# 4_cpu.net
KiCad netlist of a schematic drawn in Altium Designer
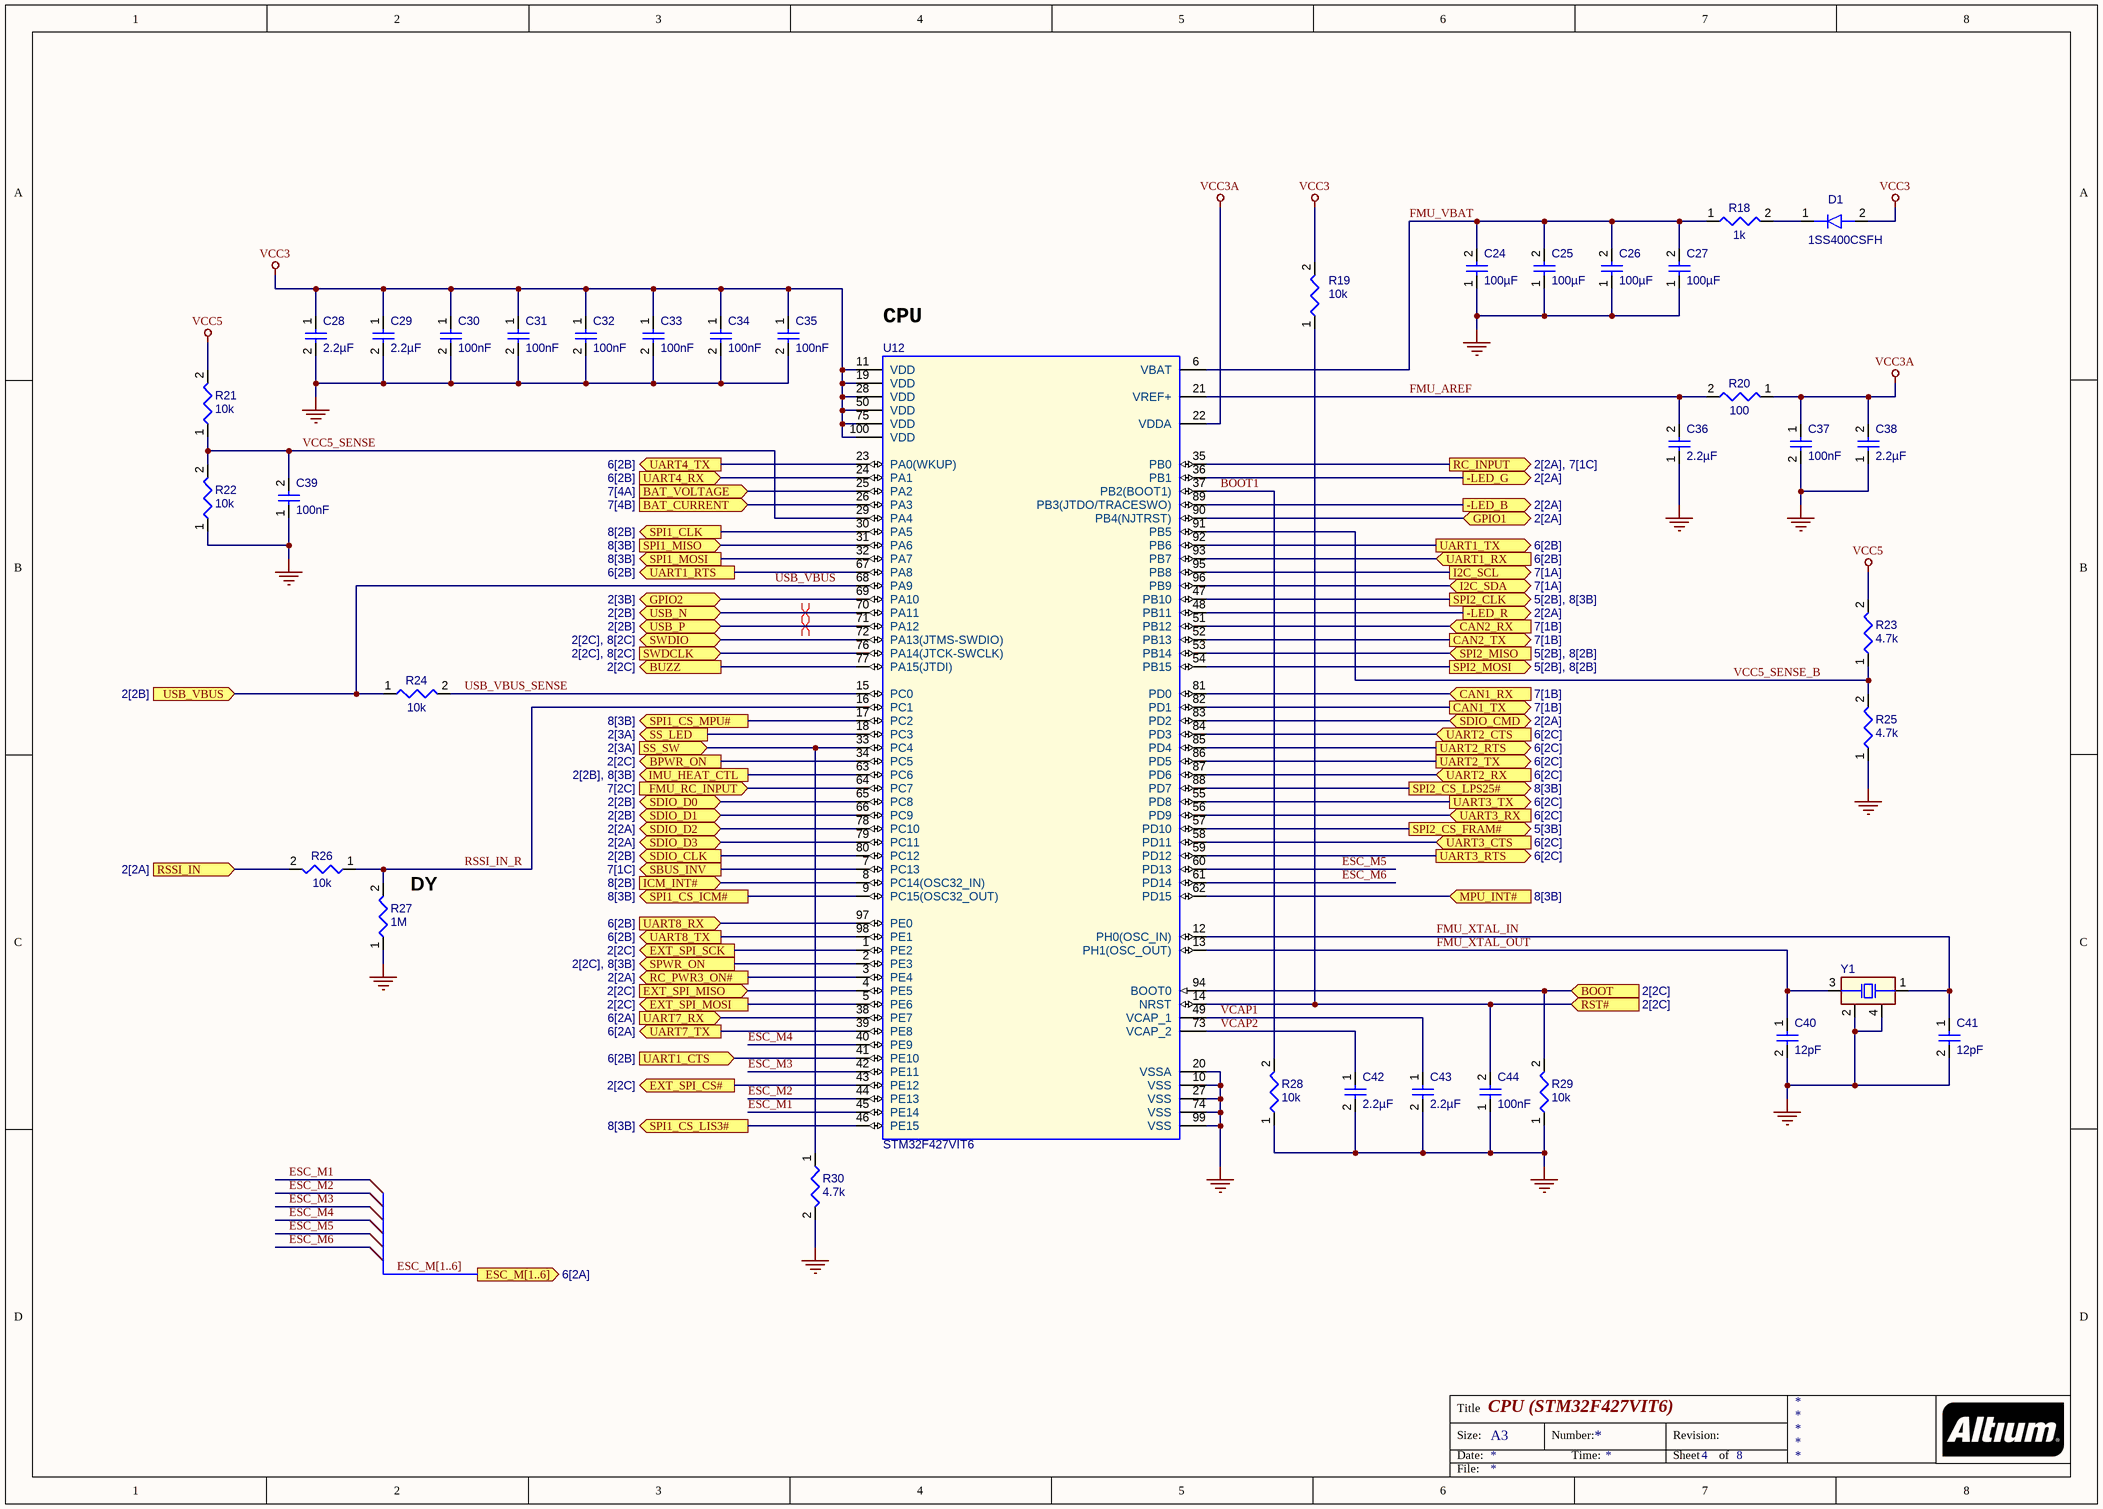
[diagram p0: 4_cpu.SchDoc]

(export (version "E")
  (design (tool "Eeschema 10.0.6"))
  (components
    (comp (ref "C24")
      (value "100µF")
      (footprint "CAPC0805(2012)145_L")
      (description "Chip Capacitor, 100µF +/-20%, 6.3V, 0805, Thickness 1.45 mm")
      (fields (field (name "TOLERANCE") "10%") (field (name "MANUFACTURER") "Murata"))
      (libsource (lib "Kame_FMU") (part "Capacitor 100µF +/-20% 6.3V 0805"))
    )
    (comp (ref "C25")
      (value "100µF")
      (footprint "CAPC0805(2012)145_L")
      (description "Chip Capacitor, 100µF +/-20%, 6.3V, 0805, Thickness 1.45 mm")
      (fields (field (name "TOLERANCE") "10%") (field (name "MANUFACTURER") "Murata"))
      (libsource (lib "Kame_FMU") (part "Capacitor 100µF +/-20% 6.3V 0805"))
    )
    (comp (ref "C26")
      (value "100µF")
      (footprint "CAPC0805(2012)145_L")
      (description "Chip Capacitor, 100µF +/-20%, 6.3V, 0805, Thickness 1.45 mm")
      (fields (field (name "TOLERANCE") "10%") (field (name "MANUFACTURER") "Murata"))
      (libsource (lib "Kame_FMU") (part "Capacitor 100µF +/-20% 6.3V 0805"))
    )
    (comp (ref "C27")
      (value "100µF")
      (footprint "CAPC0805(2012)145_L")
      (description "Chip Capacitor, 100µF +/-20%, 6.3V, 0805, Thickness 1.45 mm")
      (fields (field (name "TOLERANCE") "10%") (field (name "MANUFACTURER") "Murata"))
      (libsource (lib "Kame_FMU") (part "Capacitor 100µF +/-20% 6.3V 0805"))
    )
    (comp (ref "C28")
      (value "2.2µF")
      (footprint "CAPC0402(1005)60_L")
      (description "Chip Capacitor, 2,2µF +/-20%, 10V, 0402, Thickness 0.6 mm")
      (fields (field (name "TOLERANCE") "10%") (field (name "MANUFACTURER") "Murata"))
      (libsource (lib "Kame_FMU") (part "Capacitor 2,2µF +/-20% 10V 0402"))
    )
    (comp (ref "C29")
      (value "2.2µF")
      (footprint "CAPC0402(1005)60_L")
      (description "Chip Capacitor, 2,2µF +/-20%, 10V, 0402, Thickness 0.6 mm")
      (fields (field (name "TOLERANCE") "10%") (field (name "MANUFACTURER") "Murata"))
      (libsource (lib "Kame_FMU") (part "Capacitor 2,2µF +/-20% 10V 0402"))
    )
    (comp (ref "C30")
      (value "100nF")
      (footprint "CAPC0402(1005)60_L")
      (description "Chip Capacitor, 100nF +/-20%, 10V, 0402, Thickness 0.6 mm")
      (fields (field (name "TOLERANCE") "20%") (field (name "MANUFACTURER") "KEMET"))
      (libsource (lib "Kame_FMU") (part "Capacitor 100nF +/-20% 10V 0402"))
    )
    (comp (ref "C31")
      (value "100nF")
      (footprint "CAPC0402(1005)60_L")
      (description "Chip Capacitor, 100nF +/-20%, 10V, 0402, Thickness 0.6 mm")
      (fields (field (name "TOLERANCE") "20%") (field (name "MANUFACTURER") "KEMET"))
      (libsource (lib "Kame_FMU") (part "Capacitor 100nF +/-20% 10V 0402"))
    )
    (comp (ref "C32")
      (value "100nF")
      (footprint "CAPC0402(1005)60_L")
      (description "Chip Capacitor, 100nF +/-20%, 10V, 0402, Thickness 0.6 mm")
      (fields (field (name "TOLERANCE") "20%") (field (name "MANUFACTURER") "KEMET"))
      (libsource (lib "Kame_FMU") (part "Capacitor 100nF +/-20% 10V 0402"))
    )
    (comp (ref "C33")
      (value "100nF")
      (footprint "CAPC0402(1005)60_L")
      (description "Chip Capacitor, 100nF +/-20%, 10V, 0402, Thickness 0.6 mm")
      (fields (field (name "TOLERANCE") "20%") (field (name "MANUFACTURER") "KEMET"))
      (libsource (lib "Kame_FMU") (part "Capacitor 100nF +/-20% 10V 0402"))
    )
    (comp (ref "C34")
      (value "100nF")
      (footprint "CAPC0402(1005)60_L")
      (description "Chip Capacitor, 100nF +/-20%, 10V, 0402, Thickness 0.6 mm")
      (fields (field (name "TOLERANCE") "20%") (field (name "MANUFACTURER") "KEMET"))
      (libsource (lib "Kame_FMU") (part "Capacitor 100nF +/-20% 10V 0402"))
    )
    (comp (ref "C35")
      (value "100nF")
      (footprint "CAPC0402(1005)60_L")
      (description "Chip Capacitor, 100nF +/-20%, 10V, 0402, Thickness 0.6 mm")
      (fields (field (name "TOLERANCE") "20%") (field (name "MANUFACTURER") "KEMET"))
      (libsource (lib "Kame_FMU") (part "Capacitor 100nF +/-20% 10V 0402"))
    )
    (comp (ref "C36")
      (value "2.2µF")
      (footprint "CAPC0402(1005)60_L")
      (description "Chip Capacitor, 2,2µF +/-20%, 10V, 0402, Thickness 0.6 mm")
      (fields (field (name "TOLERANCE") "10%") (field (name "MANUFACTURER") "Murata"))
      (libsource (lib "Kame_FMU") (part "Capacitor 2,2µF +/-20% 10V 0402"))
    )
    (comp (ref "C37")
      (value "100nF")
      (footprint "CAPC0402(1005)60_L")
      (description "Chip Capacitor, 100nF +/-20%, 10V, 0402, Thickness 0.6 mm")
      (fields (field (name "TOLERANCE") "20%") (field (name "MANUFACTURER") "KEMET"))
      (libsource (lib "Kame_FMU") (part "Capacitor 100nF +/-20% 10V 0402"))
    )
    (comp (ref "C38")
      (value "2.2µF")
      (footprint "CAPC0402(1005)60_L")
      (description "Chip Capacitor, 2,2µF +/-20%, 10V, 0402, Thickness 0.6 mm")
      (fields (field (name "TOLERANCE") "10%") (field (name "MANUFACTURER") "Murata"))
      (libsource (lib "Kame_FMU") (part "Capacitor 2,2µF +/-20% 10V 0402"))
    )
    (comp (ref "C39")
      (value "100nF")
      (footprint "CAPC0402(1005)60_L")
      (description "Chip Capacitor, 100nF +/-20%, 10V, 0402, Thickness 0.6 mm")
      (fields (field (name "TOLERANCE") "20%") (field (name "MANUFACTURER") "KEMET"))
      (libsource (lib "Kame_FMU") (part "Capacitor 100nF +/-20% 10V 0402"))
    )
    (comp (ref "C40")
      (value "12pF")
      (footprint "CAPC0402(1005)33_L")
      (description "Chip Capacitor, 12pF +/-10%, 50V, 0402, Thickness 0.33 mm")
      (fields (field (name "TOLERANCE") "20%") (field (name "MANUFACTURER") "Murata"))
      (libsource (lib "Kame_FMU") (part "Capacitor 12pF +/-10% 50V 0402"))
    )
    (comp (ref "C41")
      (value "12pF")
      (footprint "CAPC0402(1005)33_L")
      (description "Chip Capacitor, 12pF +/-10%, 50V, 0402, Thickness 0.33 mm")
      (fields (field (name "TOLERANCE") "20%") (field (name "MANUFACTURER") "Murata"))
      (libsource (lib "Kame_FMU") (part "Capacitor 12pF +/-10% 50V 0402"))
    )
    (comp (ref "C42")
      (value "2.2µF")
      (footprint "CAPC0402(1005)60_L")
      (description "Chip Capacitor, 2,2µF +/-20%, 10V, 0402, Thickness 0.6 mm")
      (fields (field (name "TOLERANCE") "10%") (field (name "MANUFACTURER") "Murata"))
      (libsource (lib "Kame_FMU") (part "Capacitor 2,2µF +/-20% 10V 0402"))
    )
    (comp (ref "C43")
      (value "2.2µF")
      (footprint "CAPC0402(1005)60_L")
      (description "Chip Capacitor, 2,2µF +/-20%, 10V, 0402, Thickness 0.6 mm")
      (fields (field (name "TOLERANCE") "10%") (field (name "MANUFACTURER") "Murata"))
      (libsource (lib "Kame_FMU") (part "Capacitor 2,2µF +/-20% 10V 0402"))
    )
    (comp (ref "C44")
      (value "100nF")
      (footprint "CAPC0402(1005)60_L")
      (description "Chip Capacitor, 100nF +/-20%, 10V, 0402, Thickness 0.6 mm")
      (fields (field (name "TOLERANCE") "20%") (field (name "MANUFACTURER") "KEMET"))
      (libsource (lib "Kame_FMU") (part "Capacitor 100nF +/-20% 10V 0402"))
    )
    (comp (ref "D1")
      (value "1SS400CSFH")
      (footprint "ROHM-VMN2-2_V")
      (description "Switching Diode (High Speed Switching), 80 V, 100 mA, 2-Pin SOD-923, RoHS, Tape and Reel")
      (fields (field (name "MANUFACTURER") "Rohm") (field (name "MANUFACTURER PART NUMBER") "1SS400CSFHT2RA"))
      (libsource (lib "Kame_FMU") (part "1SS400CSFH"))
    )
    (comp (ref "R18")
      (value "1k")
      (footprint "RESC0402(1005)_L")
      (description "Chip Resistor, 1 kOhms, +/-5 %, 63 mW, -55 to 155 degC, 0402")
      (fields (field (name "TOLERANCE") "5%") (field (name "POWER") "63mW"))
      (libsource (lib "Kame_FMU") (part "Resistor 1K +/-5 % 0402 63 mW"))
    )
    (comp (ref "R19")
      (value "10k")
      (footprint "RESC0402(1005)_L")
      (description "Chip Resistor, 10 kOhms, +/-1 %, 63 mW, -55 to 125 degC, 0402")
      (fields (field (name "TOLERANCE") "1%") (field (name "POWER") "63mW"))
      (libsource (lib "Kame_FMU") (part "Resistor 10K  +/-1 % 0402 63 mW"))
    )
    (comp (ref "R20")
      (value "100")
      (footprint "RESC0402(1005)_L")
      (description "Chip Resistor, 100 Ohms, +/-1 %, 63 mW, -55 to 155 degC, 0402")
      (fields (field (name "TOLERANCE") "1%") (field (name "POWER") "63mW"))
      (libsource (lib "Kame_FMU") (part "Resistor 100R +/-1 % 0402 63 mW"))
    )
    (comp (ref "R21")
      (value "10k")
      (footprint "RESC0402(1005)_L")
      (description "Chip Resistor, 10 kOhms, +/-1 %, 63 mW, -55 to 125 degC, 0402")
      (fields (field (name "TOLERANCE") "1%") (field (name "POWER") "63mW"))
      (libsource (lib "Kame_FMU") (part "Resistor 10K  +/-1 % 0402 63 mW"))
    )
    (comp (ref "R22")
      (value "10k")
      (footprint "RESC0402(1005)_L")
      (description "Chip Resistor, 10 kOhms, +/-1 %, 63 mW, -55 to 125 degC, 0402")
      (fields (field (name "TOLERANCE") "1%") (field (name "POWER") "63mW"))
      (libsource (lib "Kame_FMU") (part "Resistor 10K  +/-1 % 0402 63 mW"))
    )
    (comp (ref "R23")
      (value "4.7k")
      (footprint "RESC0402(1005)_L")
      (description "Chip Resistor, 4,7 kOhms, +/-1 %, 63 mW, -55 to 155 degC, 0402")
      (fields (field (name "TOLERANCE") "1%") (field (name "POWER") "63mW"))
      (libsource (lib "Kame_FMU") (part "Resistor 4K7  +/-1 % 0402 63 mW"))
    )
    (comp (ref "R24")
      (value "10k")
      (footprint "RESC0402(1005)_L")
      (description "Chip Resistor, 10 kOhms, +/-1 %, 63 mW, -55 to 125 degC, 0402")
      (fields (field (name "TOLERANCE") "1%") (field (name "POWER") "63mW"))
      (libsource (lib "Kame_FMU") (part "Resistor 10K  +/-1 % 0402 63 mW"))
    )
    (comp (ref "R25")
      (value "4.7k")
      (footprint "RESC0402(1005)_L")
      (description "Chip Resistor, 4,7 kOhms, +/-1 %, 63 mW, -55 to 155 degC, 0402")
      (fields (field (name "TOLERANCE") "1%") (field (name "POWER") "63mW"))
      (libsource (lib "Kame_FMU") (part "Resistor 4K7  +/-1 % 0402 63 mW"))
    )
    (comp (ref "R26")
      (value "10k")
      (footprint "RESC0402(1005)_L")
      (description "Chip Resistor, 10 kOhms, +/-1 %, 63 mW, -55 to 125 degC, 0402")
      (fields (field (name "TOLERANCE") "1%") (field (name "POWER") "63mW"))
      (libsource (lib "Kame_FMU") (part "Resistor 10K  +/-1 % 0402 63 mW"))
    )
    (comp (ref "R27")
      (value "1M")
      (footprint "RESC0402(1005)_L")
      (description "Chip Resistor, 1 MOhms, +/-5 %, 63 mW, -55 to 155 degC, 0402")
      (fields (field (name "TOLERANCE") "5%") (field (name "POWER") "63mW"))
      (libsource (lib "Kame_FMU") (part "Resistor 1M +/-5 % 0402 63 mW"))
    )
    (comp (ref "R28")
      (value "10k")
      (footprint "RESC0402(1005)_L")
      (description "Chip Resistor, 10 kOhms, +/-1 %, 63 mW, -55 to 125 degC, 0402")
      (fields (field (name "TOLERANCE") "1%") (field (name "POWER") "63mW"))
      (libsource (lib "Kame_FMU") (part "Resistor 10K  +/-1 % 0402 63 mW"))
    )
    (comp (ref "R29")
      (value "10k")
      (footprint "RESC0402(1005)_L")
      (description "Chip Resistor, 10 kOhms, +/-1 %, 63 mW, -55 to 125 degC, 0402")
      (fields (field (name "TOLERANCE") "1%") (field (name "POWER") "63mW"))
      (libsource (lib "Kame_FMU") (part "Resistor 10K  +/-1 % 0402 63 mW"))
    )
    (comp (ref "R30")
      (value "4.7k")
      (footprint "RESC0402(1005)_L")
      (description "Chip Resistor, 4,7 kOhms, +/-1 %, 63 mW, -55 to 155 degC, 0402")
      (fields (field (name "TOLERANCE") "1%") (field (name "POWER") "63mW"))
      (libsource (lib "Kame_FMU") (part "Resistor 4K7  +/-1 % 0402 63 mW"))
    )
    (comp (ref "U12")
      (value "STM32F427VIT6")
      (footprint "STM-LQFP100")
      (libsource (lib "Kame_FMU") (part "STM32F427VIT6"))
    )
    (comp (ref "Y1")
      (value "FA-12824.0000MF10Z-W3")
      (footprint "EPSON-FA-128_V")
      (description "Crystal, 24 MHz, +/- 10 ppm, -20 to 75 degC, 4-Pin SMD, RoHS, Tape and Reel")
      (fields (field (name "MANUFACTURER") "Epson"))
      (libsource (lib "Kame_FMU") (part "FA-12824.0000MF10Z-W3"))
    )
  )
  (nets
    (net (code "1") (name "/-LED_B") (class "Default")
      (node (ref "U12") (pin "89") (pinfunction "PB3(JTDO/TRACESWO)_89") (pintype "bidirectional"))
    )
    (net (code "2") (name "/-LED_G") (class "Default")
      (node (ref "U12") (pin "36") (pinfunction "PB1_36") (pintype "bidirectional"))
    )
    (net (code "3") (name "/-LED_R") (class "Default")
      (node (ref "U12") (pin "48") (pinfunction "PB11_48") (pintype "bidirectional"))
    )
    (net (code "4") (name "/BAT_CURRENT") (class "Default")
      (node (ref "U12") (pin "26") (pinfunction "PA3_26") (pintype "bidirectional"))
    )
    (net (code "5") (name "/BAT_VOLTAGE") (class "Default")
      (node (ref "U12") (pin "25") (pinfunction "PA2_25") (pintype "bidirectional"))
    )
    (net (code "6") (name "/BOOT") (class "Default")
      (node (ref "R29") (pin "2") (pinfunction "2_2") (pintype "passive"))
      (node (ref "U12") (pin "94") (pinfunction "BOOT0_94") (pintype "input"))
    )
    (net (code "7") (name "/BOOT1") (class "Default")
      (node (ref "R28") (pin "2") (pinfunction "2_2") (pintype "passive"))
      (node (ref "U12") (pin "37") (pinfunction "PB2(BOOT1)_37") (pintype "bidirectional"))
    )
    (net (code "8") (name "/BPWR_ON") (class "Default")
      (node (ref "U12") (pin "34") (pinfunction "PC5_34") (pintype "bidirectional"))
    )
    (net (code "9") (name "/BUZZ") (class "Default")
      (node (ref "U12") (pin "77") (pinfunction "PA15(JTDI)_77") (pintype "bidirectional"))
    )
    (net (code "10") (name "/CAN1_RX") (class "Default")
      (node (ref "U12") (pin "81") (pinfunction "PD0_81") (pintype "bidirectional"))
    )
    (net (code "11") (name "/CAN1_TX") (class "Default")
      (node (ref "U12") (pin "82") (pinfunction "PD1_82") (pintype "bidirectional"))
    )
    (net (code "12") (name "/CAN2_RX") (class "Default")
      (node (ref "U12") (pin "51") (pinfunction "PB12_51") (pintype "bidirectional"))
    )
    (net (code "13") (name "/CAN2_TX") (class "Default")
      (node (ref "U12") (pin "52") (pinfunction "PB13_52") (pintype "bidirectional"))
    )
    (net (code "14") (name "/ESC_M1") (class "Default")
      (node (ref "U12") (pin "45") (pinfunction "PE14_45") (pintype "bidirectional"))
    )
    (net (code "15") (name "/ESC_M2") (class "Default")
      (node (ref "U12") (pin "44") (pinfunction "PE13_44") (pintype "bidirectional"))
    )
    (net (code "16") (name "/ESC_M3") (class "Default")
      (node (ref "U12") (pin "42") (pinfunction "PE11_42") (pintype "bidirectional"))
    )
    (net (code "17") (name "/ESC_M4") (class "Default")
      (node (ref "U12") (pin "40") (pinfunction "PE9_40") (pintype "bidirectional"))
    )
    (net (code "18") (name "/ESC_M5") (class "Default")
      (node (ref "U12") (pin "60") (pinfunction "PD13_60") (pintype "bidirectional"))
    )
    (net (code "19") (name "/ESC_M6") (class "Default")
      (node (ref "U12") (pin "61") (pinfunction "PD14_61") (pintype "bidirectional"))
    )
    (net (code "21") (name "/EXT_SPI_CS#") (class "Default")
      (node (ref "U12") (pin "43") (pinfunction "PE12_43") (pintype "bidirectional"))
    )
    (net (code "22") (name "/EXT_SPI_MISO") (class "Default")
      (node (ref "U12") (pin "4") (pinfunction "PE5_4") (pintype "bidirectional"))
    )
    (net (code "23") (name "/EXT_SPI_MOSI") (class "Default")
      (node (ref "U12") (pin "5") (pinfunction "PE6_5") (pintype "bidirectional"))
    )
    (net (code "24") (name "/EXT_SPI_SCK") (class "Default")
      (node (ref "U12") (pin "1") (pinfunction "PE2_1") (pintype "bidirectional"))
    )
    (net (code "25") (name "/FMU_AREF") (class "Default")
      (node (ref "C36") (pin "2") (pinfunction "2_2") (pintype "passive"))
      (node (ref "R20") (pin "2") (pinfunction "2_2") (pintype "passive"))
      (node (ref "U12") (pin "21") (pinfunction "VREF+_21") (pintype "power_in"))
    )
    (net (code "26") (name "/FMU_RC_INPUT") (class "Default")
      (node (ref "U12") (pin "64") (pinfunction "PC7_64") (pintype "bidirectional"))
    )
    (net (code "27") (name "/FMU_VBAT") (class "Default")
      (node (ref "C24") (pin "2") (pinfunction "2_2") (pintype "passive"))
      (node (ref "C25") (pin "2") (pinfunction "2_2") (pintype "passive"))
      (node (ref "C26") (pin "2") (pinfunction "2_2") (pintype "passive"))
      (node (ref "C27") (pin "2") (pinfunction "2_2") (pintype "passive"))
      (node (ref "R18") (pin "1") (pinfunction "1_1") (pintype "passive"))
      (node (ref "U12") (pin "6") (pinfunction "VBAT_6") (pintype "power_in"))
    )
    (net (code "28") (name "/FMU_XTAL_IN") (class "Default")
      (node (ref "C41") (pin "1") (pinfunction "1_1") (pintype "passive"))
      (node (ref "U12") (pin "12") (pinfunction "PH0(OSC_IN)_12") (pintype "bidirectional"))
      (node (ref "Y1") (pin "1") (pinfunction "X1_1") (pintype "passive"))
    )
    (net (code "29") (name "/FMU_XTAL_OUT") (class "Default")
      (node (ref "C40") (pin "1") (pinfunction "1_1") (pintype "passive"))
      (node (ref "U12") (pin "13") (pinfunction "PH1(OSC_OUT)_13") (pintype "bidirectional"))
      (node (ref "Y1") (pin "3") (pinfunction "X2_3") (pintype "passive"))
    )
    (net (code "30") (name "/GPIO1") (class "Default")
      (node (ref "U12") (pin "90") (pinfunction "PB4(NJTRST)_90") (pintype "bidirectional"))
    )
    (net (code "31") (name "/GPIO2") (class "Default")
      (node (ref "U12") (pin "69") (pinfunction "PA10_69") (pintype "bidirectional"))
    )
    (net (code "32") (name "/I2C_SCL") (class "Default")
      (node (ref "U12") (pin "95") (pinfunction "PB8_95") (pintype "bidirectional"))
    )
    (net (code "33") (name "/I2C_SDA") (class "Default")
      (node (ref "U12") (pin "96") (pinfunction "PB9_96") (pintype "bidirectional"))
    )
    (net (code "34") (name "/ICM_INT#") (class "Default")
      (node (ref "U12") (pin "8") (pinfunction "PC14(OSC32_IN)_8") (pintype "bidirectional"))
    )
    (net (code "35") (name "/IMU_HEAT_CTL") (class "Default")
      (node (ref "U12") (pin "63") (pinfunction "PC6_63") (pintype "bidirectional"))
    )
    (net (code "36") (name "/MPU_INT#") (class "Default")
      (node (ref "U12") (pin "62") (pinfunction "PD15_62") (pintype "bidirectional"))
    )
    (net (code "37") (name "/RC_INPUT") (class "Default")
      (node (ref "U12") (pin "35") (pinfunction "PB0_35") (pintype "bidirectional"))
    )
    (net (code "38") (name "/RC_PWR3_ON#") (class "Default")
      (node (ref "U12") (pin "3") (pinfunction "PE4_3") (pintype "bidirectional"))
    )
    (net (code "39") (name "/RSSI_IN") (class "Default")
      (node (ref "R26") (pin "2") (pinfunction "2_2") (pintype "passive"))
    )
    (net (code "40") (name "/RSSI_IN_R") (class "Default")
      (node (ref "R26") (pin "1") (pinfunction "1_1") (pintype "passive"))
      (node (ref "R27") (pin "2") (pinfunction "2_2") (pintype "passive"))
      (node (ref "U12") (pin "16") (pinfunction "PC1_16") (pintype "bidirectional"))
    )
    (net (code "41") (name "/RST#") (class "Default")
      (node (ref "C44") (pin "2") (pinfunction "2_2") (pintype "passive"))
      (node (ref "R19") (pin "1") (pinfunction "1_1") (pintype "passive"))
      (node (ref "U12") (pin "14") (pinfunction "NRST_14") (pintype "bidirectional"))
    )
    (net (code "42") (name "/SBUS_INV") (class "Default")
      (node (ref "U12") (pin "7") (pinfunction "PC13_7") (pintype "bidirectional"))
    )
    (net (code "43") (name "/SDIO_CLK") (class "Default")
      (node (ref "U12") (pin "80") (pinfunction "PC12_80") (pintype "bidirectional"))
    )
    (net (code "44") (name "/SDIO_CMD") (class "Default")
      (node (ref "U12") (pin "83") (pinfunction "PD2_83") (pintype "bidirectional"))
    )
    (net (code "45") (name "/SDIO_D0") (class "Default")
      (node (ref "U12") (pin "65") (pinfunction "PC8_65") (pintype "bidirectional"))
    )
    (net (code "46") (name "/SDIO_D1") (class "Default")
      (node (ref "U12") (pin "66") (pinfunction "PC9_66") (pintype "bidirectional"))
    )
    (net (code "47") (name "/SDIO_D2") (class "Default")
      (node (ref "U12") (pin "78") (pinfunction "PC10_78") (pintype "bidirectional"))
    )
    (net (code "48") (name "/SDIO_D3") (class "Default")
      (node (ref "U12") (pin "79") (pinfunction "PC11_79") (pintype "bidirectional"))
    )
    (net (code "49") (name "/SPI1_CLK") (class "Default")
      (node (ref "U12") (pin "30") (pinfunction "PA5_30") (pintype "bidirectional"))
    )
    (net (code "50") (name "/SPI1_CS_ICM#") (class "Default")
      (node (ref "U12") (pin "9") (pinfunction "PC15(OSC32_OUT)_9") (pintype "bidirectional"))
    )
    (net (code "51") (name "/SPI1_CS_LIS3#") (class "Default")
      (node (ref "U12") (pin "46") (pinfunction "PE15_46") (pintype "bidirectional"))
    )
    (net (code "52") (name "/SPI1_CS_MPU#") (class "Default")
      (node (ref "U12") (pin "17") (pinfunction "PC2_17") (pintype "bidirectional"))
    )
    (net (code "53") (name "/SPI1_MISO") (class "Default")
      (node (ref "U12") (pin "31") (pinfunction "PA6_31") (pintype "bidirectional"))
    )
    (net (code "54") (name "/SPI1_MOSI") (class "Default")
      (node (ref "U12") (pin "32") (pinfunction "PA7_32") (pintype "bidirectional"))
    )
    (net (code "55") (name "/SPI2_CLK") (class "Default")
      (node (ref "U12") (pin "47") (pinfunction "PB10_47") (pintype "bidirectional"))
    )
    (net (code "56") (name "/SPI2_CS_FRAM#") (class "Default")
      (node (ref "U12") (pin "57") (pinfunction "PD10_57") (pintype "bidirectional"))
    )
    (net (code "57") (name "/SPI2_CS_LPS25#") (class "Default")
      (node (ref "U12") (pin "88") (pinfunction "PD7_88") (pintype "bidirectional"))
    )
    (net (code "58") (name "/SPI2_MISO") (class "Default")
      (node (ref "U12") (pin "53") (pinfunction "PB14_53") (pintype "bidirectional"))
    )
    (net (code "59") (name "/SPI2_MOSI") (class "Default")
      (node (ref "U12") (pin "54") (pinfunction "PB15_54") (pintype "bidirectional"))
    )
    (net (code "60") (name "/SPWR_ON") (class "Default")
      (node (ref "U12") (pin "2") (pinfunction "PE3_2") (pintype "bidirectional"))
    )
    (net (code "61") (name "/SS_LED") (class "Default")
      (node (ref "U12") (pin "18") (pinfunction "PC3_18") (pintype "bidirectional"))
    )
    (net (code "62") (name "/SS_SW") (class "Default")
      (node (ref "R30") (pin "1") (pinfunction "1_1") (pintype "passive"))
      (node (ref "U12") (pin "33") (pinfunction "PC4_33") (pintype "bidirectional"))
    )
    (net (code "63") (name "/SWDCLK") (class "Default")
      (node (ref "U12") (pin "76") (pinfunction "PA14(JTCK-SWCLK)_76") (pintype "bidirectional"))
    )
    (net (code "64") (name "/SWDIO") (class "Default")
      (node (ref "U12") (pin "72") (pinfunction "PA13(JTMS-SWDIO)_72") (pintype "bidirectional"))
    )
    (net (code "65") (name "/UART1_CTS") (class "Default")
      (node (ref "U12") (pin "41") (pinfunction "PE10_41") (pintype "bidirectional"))
    )
    (net (code "66") (name "/UART1_RTS") (class "Default")
      (node (ref "U12") (pin "67") (pinfunction "PA8_67") (pintype "bidirectional"))
    )
    (net (code "67") (name "/UART1_RX") (class "Default")
      (node (ref "U12") (pin "93") (pinfunction "PB7_93") (pintype "bidirectional"))
    )
    (net (code "68") (name "/UART1_TX") (class "Default")
      (node (ref "U12") (pin "92") (pinfunction "PB6_92") (pintype "bidirectional"))
    )
    (net (code "69") (name "/UART2_CTS") (class "Default")
      (node (ref "U12") (pin "84") (pinfunction "PD3_84") (pintype "bidirectional"))
    )
    (net (code "70") (name "/UART2_RTS") (class "Default")
      (node (ref "U12") (pin "85") (pinfunction "PD4_85") (pintype "bidirectional"))
    )
    (net (code "71") (name "/UART2_RX") (class "Default")
      (node (ref "U12") (pin "87") (pinfunction "PD6_87") (pintype "bidirectional"))
    )
    (net (code "72") (name "/UART2_TX") (class "Default")
      (node (ref "U12") (pin "86") (pinfunction "PD5_86") (pintype "bidirectional"))
    )
    (net (code "73") (name "/UART3_CTS") (class "Default")
      (node (ref "U12") (pin "58") (pinfunction "PD11_58") (pintype "bidirectional"))
    )
    (net (code "74") (name "/UART3_RTS") (class "Default")
      (node (ref "U12") (pin "59") (pinfunction "PD12_59") (pintype "bidirectional"))
    )
    (net (code "75") (name "/UART3_RX") (class "Default")
      (node (ref "U12") (pin "56") (pinfunction "PD9_56") (pintype "bidirectional"))
    )
    (net (code "76") (name "/UART3_TX") (class "Default")
      (node (ref "U12") (pin "55") (pinfunction "PD8_55") (pintype "bidirectional"))
    )
    (net (code "77") (name "/UART4_RX") (class "Default")
      (node (ref "U12") (pin "24") (pinfunction "PA1_24") (pintype "bidirectional"))
    )
    (net (code "78") (name "/UART4_TX") (class "Default")
      (node (ref "U12") (pin "23") (pinfunction "PA0(WKUP)_23") (pintype "bidirectional"))
    )
    (net (code "79") (name "/UART7_RX") (class "Default")
      (node (ref "U12") (pin "38") (pinfunction "PE7_38") (pintype "bidirectional"))
    )
    (net (code "80") (name "/UART7_TX") (class "Default")
      (node (ref "U12") (pin "39") (pinfunction "PE8_39") (pintype "bidirectional"))
    )
    (net (code "81") (name "/UART8_RX") (class "Default")
      (node (ref "U12") (pin "97") (pinfunction "PE0_97") (pintype "bidirectional"))
    )
    (net (code "82") (name "/UART8_TX") (class "Default")
      (node (ref "U12") (pin "98") (pinfunction "PE1_98") (pintype "bidirectional"))
    )
    (net (code "83") (name "/USB_N") (class "Default")
      (node (ref "U12") (pin "70") (pinfunction "PA11_70") (pintype "bidirectional"))
    )
    (net (code "84") (name "/USB_P") (class "Default")
      (node (ref "U12") (pin "71") (pinfunction "PA12_71") (pintype "bidirectional"))
    )
    (net (code "85") (name "/USB_VBUS") (class "Default")
      (node (ref "R24") (pin "1") (pinfunction "1_1") (pintype "passive"))
      (node (ref "U12") (pin "68") (pinfunction "PA9_68") (pintype "bidirectional"))
    )
    (net (code "86") (name "/USB_VBUS_SENSE") (class "Default")
      (node (ref "R24") (pin "2") (pinfunction "2_2") (pintype "passive"))
      (node (ref "U12") (pin "15") (pinfunction "PC0_15") (pintype "bidirectional"))
    )
    (net (code "87") (name "/VCAP1") (class "Default")
      (node (ref "C43") (pin "1") (pinfunction "1_1") (pintype "passive"))
      (node (ref "U12") (pin "49") (pinfunction "VCAP_1_49") (pintype "passive"))
    )
    (net (code "88") (name "/VCAP2") (class "Default")
      (node (ref "C42") (pin "1") (pinfunction "1_1") (pintype "passive"))
      (node (ref "U12") (pin "73") (pinfunction "VCAP_2_73") (pintype "passive"))
    )
    (net (code "89") (name "/VCC5_SENSE") (class "Default")
      (node (ref "C39") (pin "2") (pinfunction "2_2") (pintype "passive"))
      (node (ref "R21") (pin "1") (pinfunction "1_1") (pintype "passive"))
      (node (ref "R22") (pin "2") (pinfunction "2_2") (pintype "passive"))
      (node (ref "U12") (pin "29") (pinfunction "PA4_29") (pintype "bidirectional"))
    )
    (net (code "90") (name "/VCC5_SENSE_B") (class "Default")
      (node (ref "R23") (pin "1") (pinfunction "1_1") (pintype "passive"))
      (node (ref "R25") (pin "2") (pinfunction "2_2") (pintype "passive"))
      (node (ref "U12") (pin "91") (pinfunction "PB5_91") (pintype "bidirectional"))
    )
    (net (code "91") (name "GND") (class "Default")
      (node (ref "C24") (pin "1") (pinfunction "1_1") (pintype "passive"))
      (node (ref "C25") (pin "1") (pinfunction "1_1") (pintype "passive"))
      (node (ref "C26") (pin "1") (pinfunction "1_1") (pintype "passive"))
      (node (ref "C27") (pin "1") (pinfunction "1_1") (pintype "passive"))
      (node (ref "C28") (pin "2") (pinfunction "2_2") (pintype "passive"))
      (node (ref "C29") (pin "2") (pinfunction "2_2") (pintype "passive"))
      (node (ref "C30") (pin "2") (pinfunction "2_2") (pintype "passive"))
      (node (ref "C31") (pin "2") (pinfunction "2_2") (pintype "passive"))
      (node (ref "C32") (pin "2") (pinfunction "2_2") (pintype "passive"))
      (node (ref "C33") (pin "2") (pinfunction "2_2") (pintype "passive"))
      (node (ref "C34") (pin "2") (pinfunction "2_2") (pintype "passive"))
      (node (ref "C35") (pin "2") (pinfunction "2_2") (pintype "passive"))
      (node (ref "C36") (pin "1") (pinfunction "1_1") (pintype "passive"))
      (node (ref "C37") (pin "2") (pinfunction "2_2") (pintype "passive"))
      (node (ref "C38") (pin "1") (pinfunction "1_1") (pintype "passive"))
      (node (ref "C39") (pin "1") (pinfunction "1_1") (pintype "passive"))
      (node (ref "C40") (pin "2") (pinfunction "2_2") (pintype "passive"))
      (node (ref "C41") (pin "2") (pinfunction "2_2") (pintype "passive"))
      (node (ref "C42") (pin "2") (pinfunction "2_2") (pintype "passive"))
      (node (ref "C43") (pin "2") (pinfunction "2_2") (pintype "passive"))
      (node (ref "C44") (pin "1") (pinfunction "1_1") (pintype "passive"))
      (node (ref "R22") (pin "1") (pinfunction "1_1") (pintype "passive"))
      (node (ref "R25") (pin "1") (pinfunction "1_1") (pintype "passive"))
      (node (ref "R27") (pin "1") (pinfunction "1_1") (pintype "passive"))
      (node (ref "R28") (pin "1") (pinfunction "1_1") (pintype "passive"))
      (node (ref "R29") (pin "1") (pinfunction "1_1") (pintype "passive"))
      (node (ref "R30") (pin "2") (pinfunction "2_2") (pintype "passive"))
      (node (ref "U12") (pin "10") (pinfunction "VSS_10") (pintype "power_in"))
      (node (ref "U12") (pin "20") (pinfunction "VSSA_20") (pintype "power_in"))
      (node (ref "U12") (pin "27") (pinfunction "VSS_27") (pintype "power_in"))
      (node (ref "U12") (pin "74") (pinfunction "VSS_74") (pintype "power_in"))
      (node (ref "U12") (pin "99") (pinfunction "VSS_99") (pintype "power_in"))
      (node (ref "Y1") (pin "2") (pinfunction "NC_2") (pintype "power_in"))
      (node (ref "Y1") (pin "4") (pinfunction "NC_4") (pintype "power_in"))
    )
    (net (code "92") (name "Net-(D1-K)") (class "Default")
      (node (ref "D1") (pin "1") (pinfunction "K_1") (pintype "passive"))
      (node (ref "R18") (pin "2") (pinfunction "2_2") (pintype "passive"))
    )
    (net (code "93") (name "VCC3") (class "Default")
      (node (ref "C28") (pin "1") (pinfunction "1_1") (pintype "passive"))
      (node (ref "C29") (pin "1") (pinfunction "1_1") (pintype "passive"))
      (node (ref "C30") (pin "1") (pinfunction "1_1") (pintype "passive"))
      (node (ref "C31") (pin "1") (pinfunction "1_1") (pintype "passive"))
      (node (ref "C32") (pin "1") (pinfunction "1_1") (pintype "passive"))
      (node (ref "C33") (pin "1") (pinfunction "1_1") (pintype "passive"))
      (node (ref "C34") (pin "1") (pinfunction "1_1") (pintype "passive"))
      (node (ref "C35") (pin "1") (pinfunction "1_1") (pintype "passive"))
      (node (ref "D1") (pin "2") (pinfunction "A_2") (pintype "passive"))
      (node (ref "R19") (pin "2") (pinfunction "2_2") (pintype "passive"))
      (node (ref "U12") (pin "100") (pinfunction "VDD_100") (pintype "power_in"))
      (node (ref "U12") (pin "11") (pinfunction "VDD_11") (pintype "power_in"))
      (node (ref "U12") (pin "19") (pinfunction "VDD_19") (pintype "power_in"))
      (node (ref "U12") (pin "28") (pinfunction "VDD_28") (pintype "power_in"))
      (node (ref "U12") (pin "50") (pinfunction "VDD_50") (pintype "power_in"))
      (node (ref "U12") (pin "75") (pinfunction "VDD_75") (pintype "power_in"))
    )
    (net (code "94") (name "VCC3A") (class "Default")
      (node (ref "C37") (pin "1") (pinfunction "1_1") (pintype "passive"))
      (node (ref "C38") (pin "2") (pinfunction "2_2") (pintype "passive"))
      (node (ref "R20") (pin "1") (pinfunction "1_1") (pintype "passive"))
      (node (ref "U12") (pin "22") (pinfunction "VDDA_22") (pintype "power_in"))
    )
    (net (code "95") (name "VCC5") (class "Default")
      (node (ref "R21") (pin "2") (pinfunction "2_2") (pintype "passive"))
      (node (ref "R23") (pin "2") (pinfunction "2_2") (pintype "passive"))
    )
  )
)
